# improved_sample-and-hold.net
KiCad netlist of a schematic drawn in EAGLE
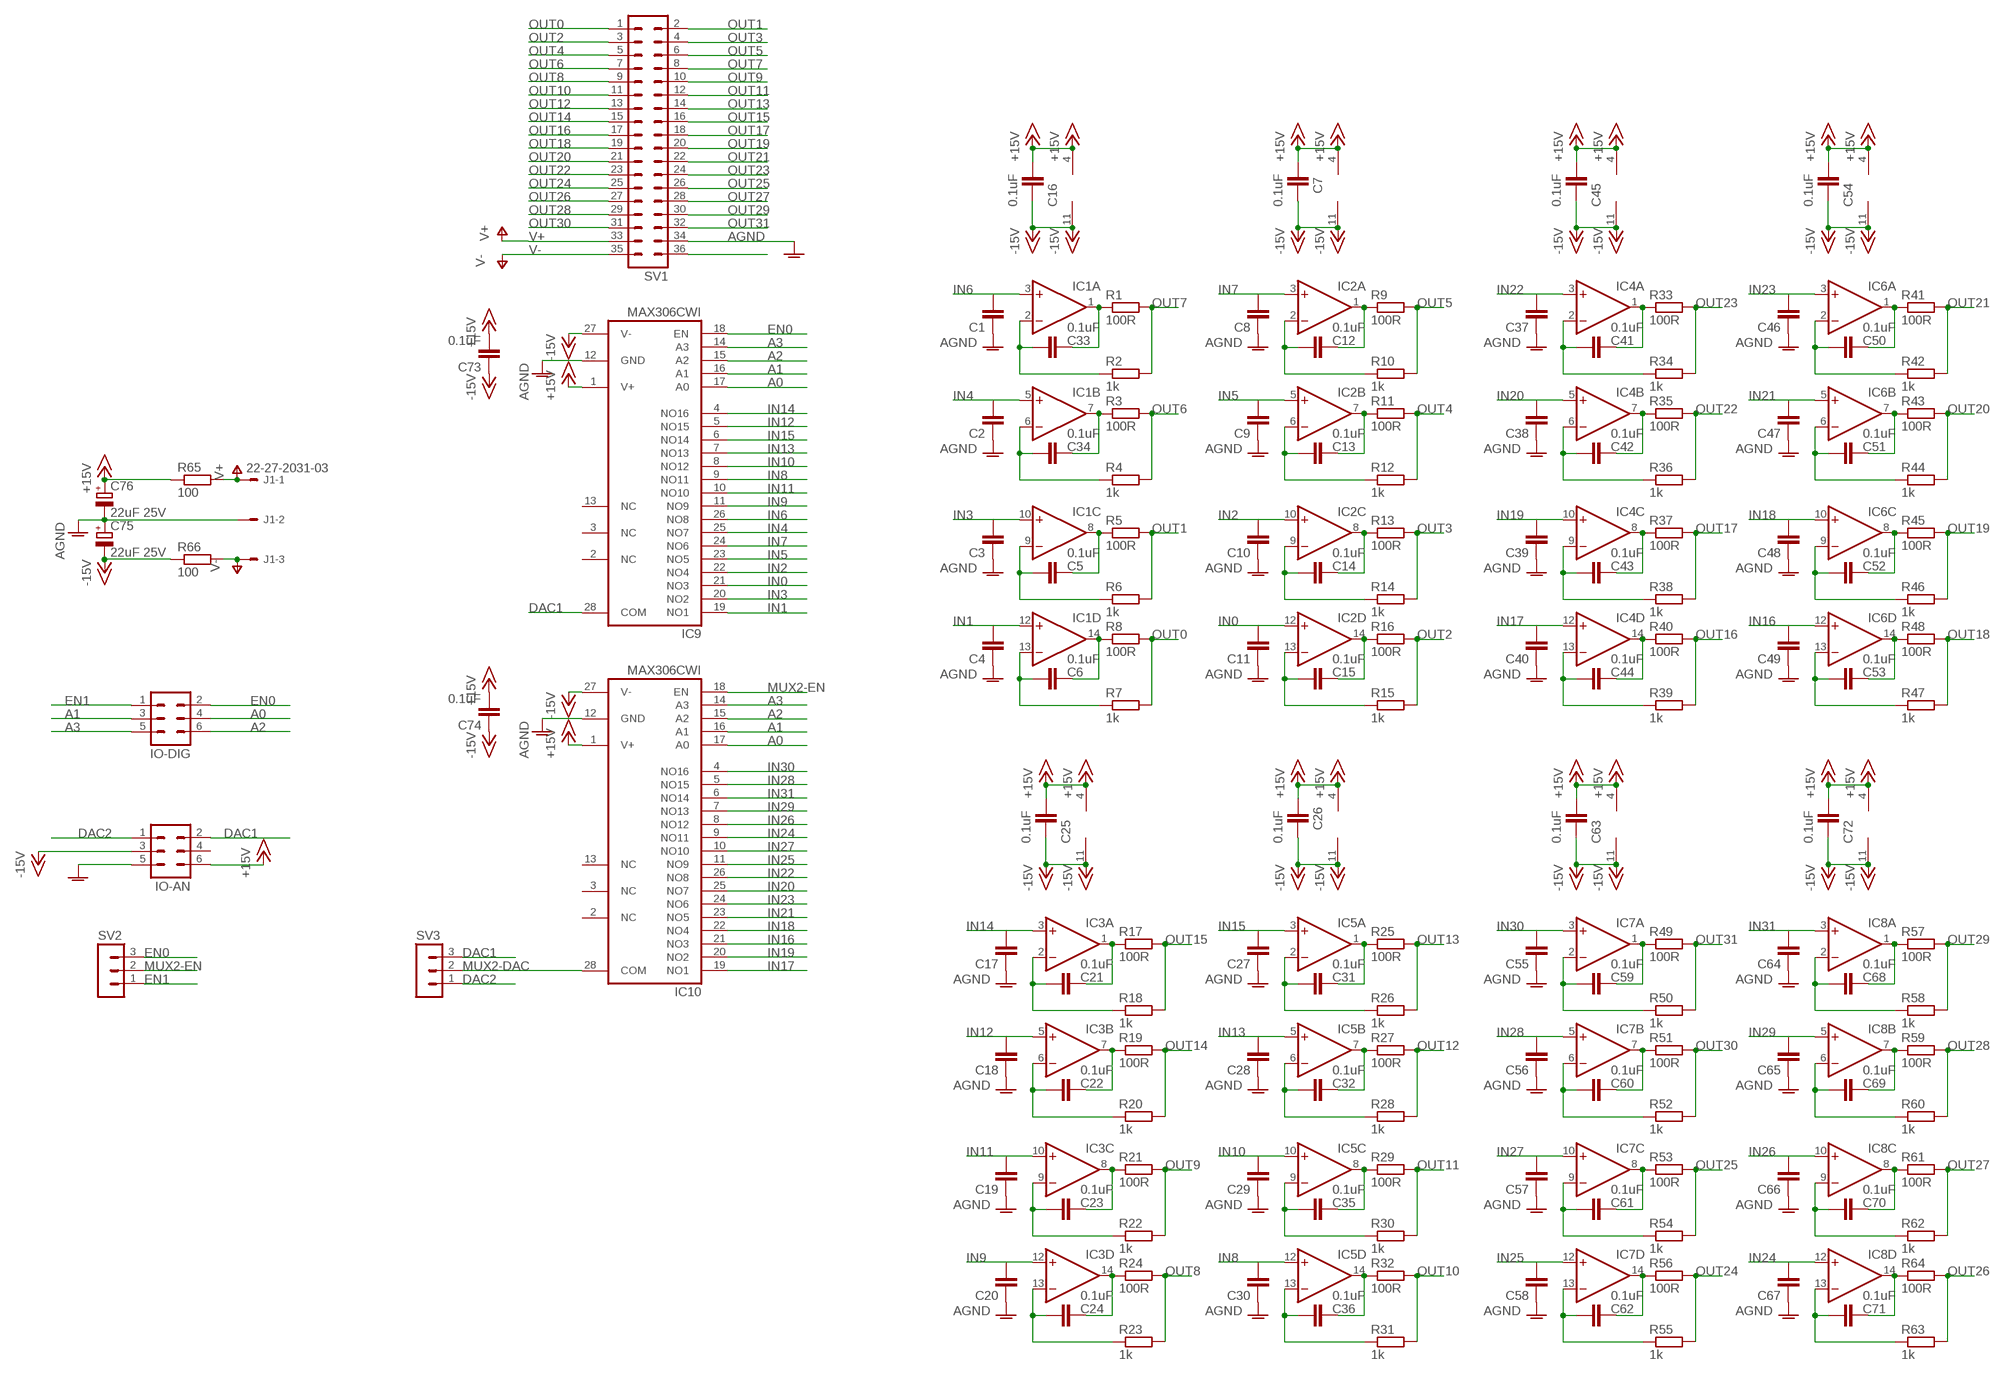
[diagram p0: schematic, sheet 1]

(export (version "E")
  (design (tool "Eeschema 10.0.6"))
  (components
    (comp (ref "C1")
      (value "C-EUC1206")
      (footprint "eagle-import:C1206")
      (libsource (lib "eagle-import") (part "C-EUC1206"))
    )
    (comp (ref "C2")
      (value "C-EUC1206")
      (footprint "eagle-import:C1206")
      (libsource (lib "eagle-import") (part "C-EUC1206"))
    )
    (comp (ref "C3")
      (value "C-EUC1206")
      (footprint "eagle-import:C1206")
      (libsource (lib "eagle-import") (part "C-EUC1206"))
    )
    (comp (ref "C4")
      (value "C-EUC1206")
      (footprint "eagle-import:C1206")
      (libsource (lib "eagle-import") (part "C-EUC1206"))
    )
    (comp (ref "C5")
      (value "0.1uF")
      (footprint "eagle-import:C0603")
      (libsource (lib "eagle-import") (part "C-EUC0603"))
    )
    (comp (ref "C6")
      (value "0.1uF")
      (footprint "eagle-import:C0603")
      (libsource (lib "eagle-import") (part "C-EUC0603"))
    )
    (comp (ref "C7")
      (value "0.1uF")
      (footprint "eagle-import:C0603")
      (libsource (lib "eagle-import") (part "C-EUC0603"))
    )
    (comp (ref "C8")
      (value "C-EUC1206")
      (footprint "eagle-import:C1206")
      (libsource (lib "eagle-import") (part "C-EUC1206"))
    )
    (comp (ref "C9")
      (value "C-EUC1206")
      (footprint "eagle-import:C1206")
      (libsource (lib "eagle-import") (part "C-EUC1206"))
    )
    (comp (ref "C10")
      (value "C-EUC1206")
      (footprint "eagle-import:C1206")
      (libsource (lib "eagle-import") (part "C-EUC1206"))
    )
    (comp (ref "C11")
      (value "C-EUC1206")
      (footprint "eagle-import:C1206")
      (libsource (lib "eagle-import") (part "C-EUC1206"))
    )
    (comp (ref "C12")
      (value "0.1uF")
      (footprint "eagle-import:C0603")
      (libsource (lib "eagle-import") (part "C-EUC0603"))
    )
    (comp (ref "C13")
      (value "0.1uF")
      (footprint "eagle-import:C0603")
      (libsource (lib "eagle-import") (part "C-EUC0603"))
    )
    (comp (ref "C14")
      (value "0.1uF")
      (footprint "eagle-import:C0603")
      (libsource (lib "eagle-import") (part "C-EUC0603"))
    )
    (comp (ref "C15")
      (value "0.1uF")
      (footprint "eagle-import:C0603")
      (libsource (lib "eagle-import") (part "C-EUC0603"))
    )
    (comp (ref "C16")
      (value "0.1uF")
      (footprint "eagle-import:C0603")
      (libsource (lib "eagle-import") (part "C-EUC0603"))
    )
    (comp (ref "C17")
      (value "C-EUC1206")
      (footprint "eagle-import:C1206")
      (libsource (lib "eagle-import") (part "C-EUC1206"))
    )
    (comp (ref "C18")
      (value "C-EUC1206")
      (footprint "eagle-import:C1206")
      (libsource (lib "eagle-import") (part "C-EUC1206"))
    )
    (comp (ref "C19")
      (value "C-EUC1206")
      (footprint "eagle-import:C1206")
      (libsource (lib "eagle-import") (part "C-EUC1206"))
    )
    (comp (ref "C20")
      (value "C-EUC1206")
      (footprint "eagle-import:C1206")
      (libsource (lib "eagle-import") (part "C-EUC1206"))
    )
    (comp (ref "C21")
      (value "0.1uF")
      (footprint "eagle-import:C0603")
      (libsource (lib "eagle-import") (part "C-EUC0603"))
    )
    (comp (ref "C22")
      (value "0.1uF")
      (footprint "eagle-import:C0603")
      (libsource (lib "eagle-import") (part "C-EUC0603"))
    )
    (comp (ref "C23")
      (value "0.1uF")
      (footprint "eagle-import:C0603")
      (libsource (lib "eagle-import") (part "C-EUC0603"))
    )
    (comp (ref "C24")
      (value "0.1uF")
      (footprint "eagle-import:C0603")
      (libsource (lib "eagle-import") (part "C-EUC0603"))
    )
    (comp (ref "C25")
      (value "0.1uF")
      (footprint "eagle-import:C0603")
      (libsource (lib "eagle-import") (part "C-EUC0603"))
    )
    (comp (ref "C26")
      (value "0.1uF")
      (footprint "eagle-import:C0603")
      (libsource (lib "eagle-import") (part "C-EUC0603"))
    )
    (comp (ref "C27")
      (value "C-EUC1206")
      (footprint "eagle-import:C1206")
      (libsource (lib "eagle-import") (part "C-EUC1206"))
    )
    (comp (ref "C28")
      (value "C-EUC1206")
      (footprint "eagle-import:C1206")
      (libsource (lib "eagle-import") (part "C-EUC1206"))
    )
    (comp (ref "C29")
      (value "C-EUC1206")
      (footprint "eagle-import:C1206")
      (libsource (lib "eagle-import") (part "C-EUC1206"))
    )
    (comp (ref "C30")
      (value "C-EUC1206")
      (footprint "eagle-import:C1206")
      (libsource (lib "eagle-import") (part "C-EUC1206"))
    )
    (comp (ref "C31")
      (value "0.1uF")
      (footprint "eagle-import:C0603")
      (libsource (lib "eagle-import") (part "C-EUC0603"))
    )
    (comp (ref "C32")
      (value "0.1uF")
      (footprint "eagle-import:C0603")
      (libsource (lib "eagle-import") (part "C-EUC0603"))
    )
    (comp (ref "C33")
      (value "0.1uF")
      (footprint "eagle-import:C0603")
      (libsource (lib "eagle-import") (part "C-EUC0603"))
    )
    (comp (ref "C34")
      (value "0.1uF")
      (footprint "eagle-import:C0603")
      (libsource (lib "eagle-import") (part "C-EUC0603"))
    )
    (comp (ref "C35")
      (value "0.1uF")
      (footprint "eagle-import:C0603")
      (libsource (lib "eagle-import") (part "C-EUC0603"))
    )
    (comp (ref "C36")
      (value "0.1uF")
      (footprint "eagle-import:C0603")
      (libsource (lib "eagle-import") (part "C-EUC0603"))
    )
    (comp (ref "C37")
      (value "C-EUC1206")
      (footprint "eagle-import:C1206")
      (libsource (lib "eagle-import") (part "C-EUC1206"))
    )
    (comp (ref "C38")
      (value "C-EUC1206")
      (footprint "eagle-import:C1206")
      (libsource (lib "eagle-import") (part "C-EUC1206"))
    )
    (comp (ref "C39")
      (value "C-EUC1206")
      (footprint "eagle-import:C1206")
      (libsource (lib "eagle-import") (part "C-EUC1206"))
    )
    (comp (ref "C40")
      (value "C-EUC1206")
      (footprint "eagle-import:C1206")
      (libsource (lib "eagle-import") (part "C-EUC1206"))
    )
    (comp (ref "C41")
      (value "0.1uF")
      (footprint "eagle-import:C0603")
      (libsource (lib "eagle-import") (part "C-EUC0603"))
    )
    (comp (ref "C42")
      (value "0.1uF")
      (footprint "eagle-import:C0603")
      (libsource (lib "eagle-import") (part "C-EUC0603"))
    )
    (comp (ref "C43")
      (value "0.1uF")
      (footprint "eagle-import:C0603")
      (libsource (lib "eagle-import") (part "C-EUC0603"))
    )
    (comp (ref "C44")
      (value "0.1uF")
      (footprint "eagle-import:C0603")
      (libsource (lib "eagle-import") (part "C-EUC0603"))
    )
    (comp (ref "C45")
      (value "0.1uF")
      (footprint "eagle-import:C0603")
      (libsource (lib "eagle-import") (part "C-EUC0603"))
    )
    (comp (ref "C46")
      (value "C-EUC1206")
      (footprint "eagle-import:C1206")
      (libsource (lib "eagle-import") (part "C-EUC1206"))
    )
    (comp (ref "C47")
      (value "C-EUC1206")
      (footprint "eagle-import:C1206")
      (libsource (lib "eagle-import") (part "C-EUC1206"))
    )
    (comp (ref "C48")
      (value "C-EUC1206")
      (footprint "eagle-import:C1206")
      (libsource (lib "eagle-import") (part "C-EUC1206"))
    )
    (comp (ref "C49")
      (value "C-EUC1206")
      (footprint "eagle-import:C1206")
      (libsource (lib "eagle-import") (part "C-EUC1206"))
    )
    (comp (ref "C50")
      (value "0.1uF")
      (footprint "eagle-import:C0603")
      (libsource (lib "eagle-import") (part "C-EUC0603"))
    )
    (comp (ref "C51")
      (value "0.1uF")
      (footprint "eagle-import:C0603")
      (libsource (lib "eagle-import") (part "C-EUC0603"))
    )
    (comp (ref "C52")
      (value "0.1uF")
      (footprint "eagle-import:C0603")
      (libsource (lib "eagle-import") (part "C-EUC0603"))
    )
    (comp (ref "C53")
      (value "0.1uF")
      (footprint "eagle-import:C0603")
      (libsource (lib "eagle-import") (part "C-EUC0603"))
    )
    (comp (ref "C54")
      (value "0.1uF")
      (footprint "eagle-import:C0603")
      (libsource (lib "eagle-import") (part "C-EUC0603"))
    )
    (comp (ref "C55")
      (value "C-EUC1206")
      (footprint "eagle-import:C1206")
      (libsource (lib "eagle-import") (part "C-EUC1206"))
    )
    (comp (ref "C56")
      (value "C-EUC1206")
      (footprint "eagle-import:C1206")
      (libsource (lib "eagle-import") (part "C-EUC1206"))
    )
    (comp (ref "C57")
      (value "C-EUC1206")
      (footprint "eagle-import:C1206")
      (libsource (lib "eagle-import") (part "C-EUC1206"))
    )
    (comp (ref "C58")
      (value "C-EUC1206")
      (footprint "eagle-import:C1206")
      (libsource (lib "eagle-import") (part "C-EUC1206"))
    )
    (comp (ref "C59")
      (value "0.1uF")
      (footprint "eagle-import:C0603")
      (libsource (lib "eagle-import") (part "C-EUC0603"))
    )
    (comp (ref "C60")
      (value "0.1uF")
      (footprint "eagle-import:C0603")
      (libsource (lib "eagle-import") (part "C-EUC0603"))
    )
    (comp (ref "C61")
      (value "0.1uF")
      (footprint "eagle-import:C0603")
      (libsource (lib "eagle-import") (part "C-EUC0603"))
    )
    (comp (ref "C62")
      (value "0.1uF")
      (footprint "eagle-import:C0603")
      (libsource (lib "eagle-import") (part "C-EUC0603"))
    )
    (comp (ref "C63")
      (value "0.1uF")
      (footprint "eagle-import:C0603")
      (libsource (lib "eagle-import") (part "C-EUC0603"))
    )
    (comp (ref "C64")
      (value "C-EUC1206")
      (footprint "eagle-import:C1206")
      (libsource (lib "eagle-import") (part "C-EUC1206"))
    )
    (comp (ref "C65")
      (value "C-EUC1206")
      (footprint "eagle-import:C1206")
      (libsource (lib "eagle-import") (part "C-EUC1206"))
    )
    (comp (ref "C66")
      (value "C-EUC1206")
      (footprint "eagle-import:C1206")
      (libsource (lib "eagle-import") (part "C-EUC1206"))
    )
    (comp (ref "C67")
      (value "C-EUC1206")
      (footprint "eagle-import:C1206")
      (libsource (lib "eagle-import") (part "C-EUC1206"))
    )
    (comp (ref "C68")
      (value "0.1uF")
      (footprint "eagle-import:C0603")
      (libsource (lib "eagle-import") (part "C-EUC0603"))
    )
    (comp (ref "C69")
      (value "0.1uF")
      (footprint "eagle-import:C0603")
      (libsource (lib "eagle-import") (part "C-EUC0603"))
    )
    (comp (ref "C70")
      (value "0.1uF")
      (footprint "eagle-import:C0603")
      (libsource (lib "eagle-import") (part "C-EUC0603"))
    )
    (comp (ref "C71")
      (value "0.1uF")
      (footprint "eagle-import:C0603")
      (libsource (lib "eagle-import") (part "C-EUC0603"))
    )
    (comp (ref "C72")
      (value "0.1uF")
      (footprint "eagle-import:C0603")
      (libsource (lib "eagle-import") (part "C-EUC0603"))
    )
    (comp (ref "C73")
      (value "0.1uF")
      (footprint "eagle-import:C0603")
      (libsource (lib "eagle-import") (part "C-EUC0603"))
    )
    (comp (ref "C74")
      (value "0.1uF")
      (footprint "eagle-import:C0603")
      (libsource (lib "eagle-import") (part "C-EUC0603"))
    )
    (comp (ref "C75")
      (value "22uF 25V")
      (footprint "eagle-import:E2-5")
      (libsource (lib "eagle-import") (part "CPOL-EUE2-5"))
    )
    (comp (ref "C76")
      (value "22uF 25V")
      (footprint "eagle-import:E2-5")
      (libsource (lib "eagle-import") (part "CPOL-EUE2-5"))
    )
    (comp (ref "IC1")
      (value "TL074D")
      (footprint "eagle-import:SO14")
      (libsource (lib "eagle-import") (part "TL074D"))
    )
    (comp (ref "IC2")
      (value "TL074D")
      (footprint "eagle-import:SO14")
      (libsource (lib "eagle-import") (part "TL074D"))
    )
    (comp (ref "IC3")
      (value "TL074D")
      (footprint "eagle-import:SO14")
      (libsource (lib "eagle-import") (part "TL074D"))
    )
    (comp (ref "IC4")
      (value "TL074D")
      (footprint "eagle-import:SO14")
      (libsource (lib "eagle-import") (part "TL074D"))
    )
    (comp (ref "IC5")
      (value "TL074D")
      (footprint "eagle-import:SO14")
      (libsource (lib "eagle-import") (part "TL074D"))
    )
    (comp (ref "IC6")
      (value "TL074D")
      (footprint "eagle-import:SO14")
      (libsource (lib "eagle-import") (part "TL074D"))
    )
    (comp (ref "IC7")
      (value "TL074D")
      (footprint "eagle-import:SO14")
      (libsource (lib "eagle-import") (part "TL074D"))
    )
    (comp (ref "IC8")
      (value "TL074D")
      (footprint "eagle-import:SO14")
      (libsource (lib "eagle-import") (part "TL074D"))
    )
    (comp (ref "IC9")
      (value "MAX306CWI")
      (footprint "eagle-import:SO28L")
      (fields (field (name "MF") "MAXIM"))
      (libsource (lib "eagle-import") (part "MAX306CWI"))
    )
    (comp (ref "IC10")
      (value "MAX306CWI")
      (footprint "eagle-import:SO28L")
      (fields (field (name "MF") "MAXIM"))
      (libsource (lib "eagle-import") (part "MAX306CWI"))
    )
    (comp (ref "IO-AN")
      (value "MA03-2")
      (footprint "eagle-import:MA03-2")
      (libsource (lib "eagle-import") (part "MA03-2"))
    )
    (comp (ref "IO-DIG")
      (value "MA03-2")
      (footprint "eagle-import:MA03-2")
      (libsource (lib "eagle-import") (part "MA03-2"))
    )
    (comp (ref "J1")
      (value "22-27-2031-03")
      (footprint "eagle-import:6410-03")
      (libsource (lib "eagle-import") (part "22-?-0327-2031"))
    )
    (comp (ref "R1")
      (value "100R")
      (footprint "eagle-import:R0603")
      (libsource (lib "eagle-import") (part "R-EU_R0603"))
    )
    (comp (ref "R2")
      (value "1k")
      (footprint "eagle-import:R0603")
      (libsource (lib "eagle-import") (part "R-EU_R0603"))
    )
    (comp (ref "R3")
      (value "100R")
      (footprint "eagle-import:R0603")
      (libsource (lib "eagle-import") (part "R-EU_R0603"))
    )
    (comp (ref "R4")
      (value "1k")
      (footprint "eagle-import:R0603")
      (libsource (lib "eagle-import") (part "R-EU_R0603"))
    )
    (comp (ref "R5")
      (value "100R")
      (footprint "eagle-import:R0603")
      (libsource (lib "eagle-import") (part "R-EU_R0603"))
    )
    (comp (ref "R6")
      (value "1k")
      (footprint "eagle-import:R0603")
      (libsource (lib "eagle-import") (part "R-EU_R0603"))
    )
    (comp (ref "R7")
      (value "1k")
      (footprint "eagle-import:R0603")
      (libsource (lib "eagle-import") (part "R-EU_R0603"))
    )
    (comp (ref "R8")
      (value "100R")
      (footprint "eagle-import:R0603")
      (libsource (lib "eagle-import") (part "R-EU_R0603"))
    )
    (comp (ref "R9")
      (value "100R")
      (footprint "eagle-import:R0603")
      (libsource (lib "eagle-import") (part "R-EU_R0603"))
    )
    (comp (ref "R10")
      (value "1k")
      (footprint "eagle-import:R0603")
      (libsource (lib "eagle-import") (part "R-EU_R0603"))
    )
    (comp (ref "R11")
      (value "100R")
      (footprint "eagle-import:R0603")
      (libsource (lib "eagle-import") (part "R-EU_R0603"))
    )
    (comp (ref "R12")
      (value "1k")
      (footprint "eagle-import:R0603")
      (libsource (lib "eagle-import") (part "R-EU_R0603"))
    )
    (comp (ref "R13")
      (value "100R")
      (footprint "eagle-import:R0603")
      (libsource (lib "eagle-import") (part "R-EU_R0603"))
    )
    (comp (ref "R14")
      (value "1k")
      (footprint "eagle-import:R0603")
      (libsource (lib "eagle-import") (part "R-EU_R0603"))
    )
    (comp (ref "R15")
      (value "1k")
      (footprint "eagle-import:R0603")
      (libsource (lib "eagle-import") (part "R-EU_R0603"))
    )
    (comp (ref "R16")
      (value "100R")
      (footprint "eagle-import:R0603")
      (libsource (lib "eagle-import") (part "R-EU_R0603"))
    )
    (comp (ref "R17")
      (value "100R")
      (footprint "eagle-import:R0603")
      (libsource (lib "eagle-import") (part "R-EU_R0603"))
    )
    (comp (ref "R18")
      (value "1k")
      (footprint "eagle-import:R0603")
      (libsource (lib "eagle-import") (part "R-EU_R0603"))
    )
    (comp (ref "R19")
      (value "100R")
      (footprint "eagle-import:R0603")
      (libsource (lib "eagle-import") (part "R-EU_R0603"))
    )
    (comp (ref "R20")
      (value "1k")
      (footprint "eagle-import:R0603")
      (libsource (lib "eagle-import") (part "R-EU_R0603"))
    )
    (comp (ref "R21")
      (value "100R")
      (footprint "eagle-import:R0603")
      (libsource (lib "eagle-import") (part "R-EU_R0603"))
    )
    (comp (ref "R22")
      (value "1k")
      (footprint "eagle-import:R0603")
      (libsource (lib "eagle-import") (part "R-EU_R0603"))
    )
    (comp (ref "R23")
      (value "1k")
      (footprint "eagle-import:R0603")
      (libsource (lib "eagle-import") (part "R-EU_R0603"))
    )
    (comp (ref "R24")
      (value "100R")
      (footprint "eagle-import:R0603")
      (libsource (lib "eagle-import") (part "R-EU_R0603"))
    )
    (comp (ref "R25")
      (value "100R")
      (footprint "eagle-import:R0603")
      (libsource (lib "eagle-import") (part "R-EU_R0603"))
    )
    (comp (ref "R26")
      (value "1k")
      (footprint "eagle-import:R0603")
      (libsource (lib "eagle-import") (part "R-EU_R0603"))
    )
    (comp (ref "R27")
      (value "100R")
      (footprint "eagle-import:R0603")
      (libsource (lib "eagle-import") (part "R-EU_R0603"))
    )
    (comp (ref "R28")
      (value "1k")
      (footprint "eagle-import:R0603")
      (libsource (lib "eagle-import") (part "R-EU_R0603"))
    )
    (comp (ref "R29")
      (value "100R")
      (footprint "eagle-import:R0603")
      (libsource (lib "eagle-import") (part "R-EU_R0603"))
    )
    (comp (ref "R30")
      (value "1k")
      (footprint "eagle-import:R0603")
      (libsource (lib "eagle-import") (part "R-EU_R0603"))
    )
    (comp (ref "R31")
      (value "1k")
      (footprint "eagle-import:R0603")
      (libsource (lib "eagle-import") (part "R-EU_R0603"))
    )
    (comp (ref "R32")
      (value "100R")
      (footprint "eagle-import:R0603")
      (libsource (lib "eagle-import") (part "R-EU_R0603"))
    )
    (comp (ref "R33")
      (value "100R")
      (footprint "eagle-import:R0603")
      (libsource (lib "eagle-import") (part "R-EU_R0603"))
    )
    (comp (ref "R34")
      (value "1k")
      (footprint "eagle-import:R0603")
      (libsource (lib "eagle-import") (part "R-EU_R0603"))
    )
    (comp (ref "R35")
      (value "100R")
      (footprint "eagle-import:R0603")
      (libsource (lib "eagle-import") (part "R-EU_R0603"))
    )
    (comp (ref "R36")
      (value "1k")
      (footprint "eagle-import:R0603")
      (libsource (lib "eagle-import") (part "R-EU_R0603"))
    )
    (comp (ref "R37")
      (value "100R")
      (footprint "eagle-import:R0603")
      (libsource (lib "eagle-import") (part "R-EU_R0603"))
    )
    (comp (ref "R38")
      (value "1k")
      (footprint "eagle-import:R0603")
      (libsource (lib "eagle-import") (part "R-EU_R0603"))
    )
    (comp (ref "R39")
      (value "1k")
      (footprint "eagle-import:R0603")
      (libsource (lib "eagle-import") (part "R-EU_R0603"))
    )
    (comp (ref "R40")
      (value "100R")
      (footprint "eagle-import:R0603")
      (libsource (lib "eagle-import") (part "R-EU_R0603"))
    )
    (comp (ref "R41")
      (value "100R")
      (footprint "eagle-import:R0603")
      (libsource (lib "eagle-import") (part "R-EU_R0603"))
    )
    (comp (ref "R42")
      (value "1k")
      (footprint "eagle-import:R0603")
      (libsource (lib "eagle-import") (part "R-EU_R0603"))
    )
    (comp (ref "R43")
      (value "100R")
      (footprint "eagle-import:R0603")
      (libsource (lib "eagle-import") (part "R-EU_R0603"))
    )
    (comp (ref "R44")
      (value "1k")
      (footprint "eagle-import:R0603")
      (libsource (lib "eagle-import") (part "R-EU_R0603"))
    )
    (comp (ref "R45")
      (value "100R")
      (footprint "eagle-import:R0603")
      (libsource (lib "eagle-import") (part "R-EU_R0603"))
    )
    (comp (ref "R46")
      (value "1k")
      (footprint "eagle-import:R0603")
      (libsource (lib "eagle-import") (part "R-EU_R0603"))
    )
    (comp (ref "R47")
      (value "1k")
      (footprint "eagle-import:R0603")
      (libsource (lib "eagle-import") (part "R-EU_R0603"))
    )
    (comp (ref "R48")
      (value "100R")
      (footprint "eagle-import:R0603")
      (libsource (lib "eagle-import") (part "R-EU_R0603"))
    )
    (comp (ref "R49")
      (value "100R")
      (footprint "eagle-import:R0603")
      (libsource (lib "eagle-import") (part "R-EU_R0603"))
    )
    (comp (ref "R50")
      (value "1k")
      (footprint "eagle-import:R0603")
      (libsource (lib "eagle-import") (part "R-EU_R0603"))
    )
    (comp (ref "R51")
      (value "100R")
      (footprint "eagle-import:R0603")
      (libsource (lib "eagle-import") (part "R-EU_R0603"))
    )
    (comp (ref "R52")
      (value "1k")
      (footprint "eagle-import:R0603")
      (libsource (lib "eagle-import") (part "R-EU_R0603"))
    )
    (comp (ref "R53")
      (value "100R")
      (footprint "eagle-import:R0603")
      (libsource (lib "eagle-import") (part "R-EU_R0603"))
    )
    (comp (ref "R54")
      (value "1k")
      (footprint "eagle-import:R0603")
      (libsource (lib "eagle-import") (part "R-EU_R0603"))
    )
    (comp (ref "R55")
      (value "1k")
      (footprint "eagle-import:R0603")
      (libsource (lib "eagle-import") (part "R-EU_R0603"))
    )
    (comp (ref "R56")
      (value "100R")
      (footprint "eagle-import:R0603")
      (libsource (lib "eagle-import") (part "R-EU_R0603"))
    )
    (comp (ref "R57")
      (value "100R")
      (footprint "eagle-import:R0603")
      (libsource (lib "eagle-import") (part "R-EU_R0603"))
    )
    (comp (ref "R58")
      (value "1k")
      (footprint "eagle-import:R0603")
      (libsource (lib "eagle-import") (part "R-EU_R0603"))
    )
    (comp (ref "R59")
      (value "100R")
      (footprint "eagle-import:R0603")
      (libsource (lib "eagle-import") (part "R-EU_R0603"))
    )
    (comp (ref "R60")
      (value "1k")
      (footprint "eagle-import:R0603")
      (libsource (lib "eagle-import") (part "R-EU_R0603"))
    )
    (comp (ref "R61")
      (value "100R")
      (footprint "eagle-import:R0603")
      (libsource (lib "eagle-import") (part "R-EU_R0603"))
    )
    (comp (ref "R62")
      (value "1k")
      (footprint "eagle-import:R0603")
      (libsource (lib "eagle-import") (part "R-EU_R0603"))
    )
    (comp (ref "R63")
      (value "1k")
      (footprint "eagle-import:R0603")
      (libsource (lib "eagle-import") (part "R-EU_R0603"))
    )
    (comp (ref "R64")
      (value "100R")
      (footprint "eagle-import:R0603")
      (libsource (lib "eagle-import") (part "R-EU_R0603"))
    )
    (comp (ref "R65")
      (value "100")
      (footprint "eagle-import:0207_7")
      (libsource (lib "eagle-import") (part "R-EU_0207/7"))
    )
    (comp (ref "R66")
      (value "100")
      (footprint "eagle-import:0207_7")
      (libsource (lib "eagle-import") (part "R-EU_0207/7"))
    )
    (comp (ref "SV1")
      (value "MA18-2")
      (footprint "eagle-import:MA18-2")
      (libsource (lib "eagle-import") (part "MA18-2"))
    )
    (comp (ref "SV2")
      (value "MA03-1")
      (footprint "eagle-import:MA03-1")
      (libsource (lib "eagle-import") (part "MA03-1"))
    )
    (comp (ref "SV3")
      (value "MA03-1")
      (footprint "eagle-import:MA03-1")
      (libsource (lib "eagle-import") (part "MA03-1"))
    )
  )
  (nets
    (net (code "1") (name "+15V") (class "Default")
      (node (ref "C16") (pin "1") (pinfunction "1_1") (pintype "passive"))
      (node (ref "C25") (pin "1") (pinfunction "1_1") (pintype "passive"))
      (node (ref "C26") (pin "1") (pinfunction "1_1") (pintype "passive"))
      (node (ref "C45") (pin "1") (pinfunction "1_1") (pintype "passive"))
      (node (ref "C54") (pin "1") (pinfunction "1_1") (pintype "passive"))
      (node (ref "C63") (pin "1") (pinfunction "1_1") (pintype "passive"))
      (node (ref "C7") (pin "1") (pinfunction "1_1") (pintype "passive"))
      (node (ref "C72") (pin "1") (pinfunction "1_1") (pintype "passive"))
      (node (ref "C73") (pin "2") (pinfunction "2_2") (pintype "passive"))
      (node (ref "C74") (pin "2") (pinfunction "2_2") (pintype "passive"))
      (node (ref "C76") (pin "+") (pinfunction "+_+") (pintype "passive"))
      (node (ref "IC1") (pin "4") (pinfunction "V+_4") (pintype "power_in"))
      (node (ref "IC10") (pin "1") (pinfunction "V+_1") (pintype "power_in"))
      (node (ref "IC2") (pin "4") (pinfunction "V+_4") (pintype "power_in"))
      (node (ref "IC3") (pin "4") (pinfunction "V+_4") (pintype "power_in"))
      (node (ref "IC4") (pin "4") (pinfunction "V+_4") (pintype "power_in"))
      (node (ref "IC5") (pin "4") (pinfunction "V+_4") (pintype "power_in"))
      (node (ref "IC6") (pin "4") (pinfunction "V+_4") (pintype "power_in"))
      (node (ref "IC7") (pin "4") (pinfunction "V+_4") (pintype "power_in"))
      (node (ref "IC8") (pin "4") (pinfunction "V+_4") (pintype "power_in"))
      (node (ref "IC9") (pin "1") (pinfunction "V+_1") (pintype "power_in"))
      (node (ref "IO-AN") (pin "6") (pinfunction "6_6") (pintype "passive"))
      (node (ref "R65") (pin "1") (pinfunction "1_1") (pintype "passive"))
    )
    (net (code "2") (name "-15V") (class "Default")
      (node (ref "C16") (pin "2") (pinfunction "2_2") (pintype "passive"))
      (node (ref "C25") (pin "2") (pinfunction "2_2") (pintype "passive"))
      (node (ref "C26") (pin "2") (pinfunction "2_2") (pintype "passive"))
      (node (ref "C45") (pin "2") (pinfunction "2_2") (pintype "passive"))
      (node (ref "C54") (pin "2") (pinfunction "2_2") (pintype "passive"))
      (node (ref "C63") (pin "2") (pinfunction "2_2") (pintype "passive"))
      (node (ref "C7") (pin "2") (pinfunction "2_2") (pintype "passive"))
      (node (ref "C72") (pin "2") (pinfunction "2_2") (pintype "passive"))
      (node (ref "C73") (pin "1") (pinfunction "1_1") (pintype "passive"))
      (node (ref "C74") (pin "1") (pinfunction "1_1") (pintype "passive"))
      (node (ref "C75") (pin "-") (pinfunction "-_-") (pintype "passive"))
      (node (ref "IC1") (pin "11") (pinfunction "V-_11") (pintype "power_in"))
      (node (ref "IC10") (pin "27") (pinfunction "V-_27") (pintype "power_in"))
      (node (ref "IC2") (pin "11") (pinfunction "V-_11") (pintype "power_in"))
      (node (ref "IC3") (pin "11") (pinfunction "V-_11") (pintype "power_in"))
      (node (ref "IC4") (pin "11") (pinfunction "V-_11") (pintype "power_in"))
      (node (ref "IC5") (pin "11") (pinfunction "V-_11") (pintype "power_in"))
      (node (ref "IC6") (pin "11") (pinfunction "V-_11") (pintype "power_in"))
      (node (ref "IC7") (pin "11") (pinfunction "V-_11") (pintype "power_in"))
      (node (ref "IC8") (pin "11") (pinfunction "V-_11") (pintype "power_in"))
      (node (ref "IC9") (pin "27") (pinfunction "V-_27") (pintype "power_in"))
      (node (ref "IO-AN") (pin "3") (pinfunction "3_3") (pintype "passive"))
      (node (ref "R66") (pin "1") (pinfunction "1_1") (pintype "passive"))
    )
    (net (code "3") (name "/A0") (class "Default")
      (node (ref "IC10") (pin "17") (pinfunction "A0_17") (pintype "input"))
      (node (ref "IC9") (pin "17") (pinfunction "A0_17") (pintype "input"))
      (node (ref "IO-DIG") (pin "4") (pinfunction "4_4") (pintype "passive"))
    )
    (net (code "4") (name "/A1") (class "Default")
      (node (ref "IC10") (pin "16") (pinfunction "A1_16") (pintype "input"))
      (node (ref "IC9") (pin "16") (pinfunction "A1_16") (pintype "input"))
      (node (ref "IO-DIG") (pin "3") (pinfunction "3_3") (pintype "passive"))
    )
    (net (code "5") (name "/A2") (class "Default")
      (node (ref "IC10") (pin "15") (pinfunction "A2_15") (pintype "input"))
      (node (ref "IC9") (pin "15") (pinfunction "A2_15") (pintype "input"))
      (node (ref "IO-DIG") (pin "6") (pinfunction "6_6") (pintype "passive"))
    )
    (net (code "6") (name "/A3") (class "Default")
      (node (ref "IC10") (pin "14") (pinfunction "A3_14") (pintype "input"))
      (node (ref "IC9") (pin "14") (pinfunction "A3_14") (pintype "input"))
      (node (ref "IO-DIG") (pin "5") (pinfunction "5_5") (pintype "passive"))
    )
    (net (code "7") (name "/DAC1") (class "Default")
      (node (ref "IC9") (pin "28") (pinfunction "COM_28") (pintype "passive"))
      (node (ref "IO-AN") (pin "2") (pinfunction "2_2") (pintype "passive"))
      (node (ref "SV3") (pin "3") (pinfunction "3_3") (pintype "passive"))
    )
    (net (code "8") (name "/DAC2") (class "Default")
      (node (ref "IO-AN") (pin "1") (pinfunction "1_1") (pintype "passive"))
      (node (ref "SV3") (pin "1") (pinfunction "1_1") (pintype "passive"))
    )
    (net (code "9") (name "/EN0") (class "Default")
      (node (ref "IC9") (pin "18") (pinfunction "EN_18") (pintype "input"))
      (node (ref "IO-DIG") (pin "2") (pinfunction "2_2") (pintype "passive"))
      (node (ref "SV2") (pin "3") (pinfunction "3_3") (pintype "passive"))
    )
    (net (code "10") (name "/EN1") (class "Default")
      (node (ref "IO-DIG") (pin "1") (pinfunction "1_1") (pintype "passive"))
      (node (ref "SV2") (pin "1") (pinfunction "1_1") (pintype "passive"))
    )
    (net (code "11") (name "/IN0") (class "Default")
      (node (ref "C11") (pin "2") (pinfunction "2_2") (pintype "passive"))
      (node (ref "IC2") (pin "12") (pinfunction "+IN_12") (pintype "input"))
      (node (ref "IC9") (pin "21") (pinfunction "NO3_21") (pintype "passive"))
    )
    (net (code "12") (name "/IN1") (class "Default")
      (node (ref "C4") (pin "2") (pinfunction "2_2") (pintype "passive"))
      (node (ref "IC1") (pin "12") (pinfunction "+IN_12") (pintype "input"))
      (node (ref "IC9") (pin "19") (pinfunction "NO1_19") (pintype "passive"))
    )
    (net (code "13") (name "/IN2") (class "Default")
      (node (ref "C10") (pin "2") (pinfunction "2_2") (pintype "passive"))
      (node (ref "IC2") (pin "10") (pinfunction "+IN_10") (pintype "input"))
      (node (ref "IC9") (pin "22") (pinfunction "NO4_22") (pintype "passive"))
    )
    (net (code "14") (name "/IN3") (class "Default")
      (node (ref "C3") (pin "2") (pinfunction "2_2") (pintype "passive"))
      (node (ref "IC1") (pin "10") (pinfunction "+IN_10") (pintype "input"))
      (node (ref "IC9") (pin "20") (pinfunction "NO2_20") (pintype "passive"))
    )
    (net (code "15") (name "/IN4") (class "Default")
      (node (ref "C2") (pin "2") (pinfunction "2_2") (pintype "passive"))
      (node (ref "IC1") (pin "5") (pinfunction "+IN_5") (pintype "input"))
      (node (ref "IC9") (pin "25") (pinfunction "NO7_25") (pintype "passive"))
    )
    (net (code "16") (name "/IN5") (class "Default")
      (node (ref "C9") (pin "2") (pinfunction "2_2") (pintype "passive"))
      (node (ref "IC2") (pin "5") (pinfunction "+IN_5") (pintype "input"))
      (node (ref "IC9") (pin "23") (pinfunction "NO5_23") (pintype "passive"))
    )
    (net (code "17") (name "/IN6") (class "Default")
      (node (ref "C1") (pin "2") (pinfunction "2_2") (pintype "passive"))
      (node (ref "IC1") (pin "3") (pinfunction "+IN_3") (pintype "input"))
      (node (ref "IC9") (pin "26") (pinfunction "NO8_26") (pintype "passive"))
    )
    (net (code "18") (name "/IN7") (class "Default")
      (node (ref "C8") (pin "2") (pinfunction "2_2") (pintype "passive"))
      (node (ref "IC2") (pin "3") (pinfunction "+IN_3") (pintype "input"))
      (node (ref "IC9") (pin "24") (pinfunction "NO6_24") (pintype "passive"))
    )
    (net (code "19") (name "/IN8") (class "Default")
      (node (ref "C30") (pin "2") (pinfunction "2_2") (pintype "passive"))
      (node (ref "IC5") (pin "12") (pinfunction "+IN_12") (pintype "input"))
      (node (ref "IC9") (pin "9") (pinfunction "NO11_9") (pintype "passive"))
    )
    (net (code "20") (name "/IN9") (class "Default")
      (node (ref "C20") (pin "2") (pinfunction "2_2") (pintype "passive"))
      (node (ref "IC3") (pin "12") (pinfunction "+IN_12") (pintype "input"))
      (node (ref "IC9") (pin "11") (pinfunction "NO9_11") (pintype "passive"))
    )
    (net (code "21") (name "/IN10") (class "Default")
      (node (ref "C29") (pin "2") (pinfunction "2_2") (pintype "passive"))
      (node (ref "IC5") (pin "10") (pinfunction "+IN_10") (pintype "input"))
      (node (ref "IC9") (pin "8") (pinfunction "NO12_8") (pintype "passive"))
    )
    (net (code "22") (name "/IN11") (class "Default")
      (node (ref "C19") (pin "2") (pinfunction "2_2") (pintype "passive"))
      (node (ref "IC3") (pin "10") (pinfunction "+IN_10") (pintype "input"))
      (node (ref "IC9") (pin "10") (pinfunction "NO10_10") (pintype "passive"))
    )
    (net (code "23") (name "/IN12") (class "Default")
      (node (ref "C18") (pin "2") (pinfunction "2_2") (pintype "passive"))
      (node (ref "IC3") (pin "5") (pinfunction "+IN_5") (pintype "input"))
      (node (ref "IC9") (pin "5") (pinfunction "NO15_5") (pintype "passive"))
    )
    (net (code "24") (name "/IN13") (class "Default")
      (node (ref "C28") (pin "2") (pinfunction "2_2") (pintype "passive"))
      (node (ref "IC5") (pin "5") (pinfunction "+IN_5") (pintype "input"))
      (node (ref "IC9") (pin "7") (pinfunction "NO13_7") (pintype "passive"))
    )
    (net (code "25") (name "/IN14") (class "Default")
      (node (ref "C17") (pin "2") (pinfunction "2_2") (pintype "passive"))
      (node (ref "IC3") (pin "3") (pinfunction "+IN_3") (pintype "input"))
      (node (ref "IC9") (pin "4") (pinfunction "NO16_4") (pintype "passive"))
    )
    (net (code "26") (name "/IN15") (class "Default")
      (node (ref "C27") (pin "2") (pinfunction "2_2") (pintype "passive"))
      (node (ref "IC5") (pin "3") (pinfunction "+IN_3") (pintype "input"))
      (node (ref "IC9") (pin "6") (pinfunction "NO14_6") (pintype "passive"))
    )
    (net (code "27") (name "/IN16") (class "Default")
      (node (ref "C49") (pin "2") (pinfunction "2_2") (pintype "passive"))
      (node (ref "IC10") (pin "21") (pinfunction "NO3_21") (pintype "passive"))
      (node (ref "IC6") (pin "12") (pinfunction "+IN_12") (pintype "input"))
    )
    (net (code "28") (name "/IN17") (class "Default")
      (node (ref "C40") (pin "2") (pinfunction "2_2") (pintype "passive"))
      (node (ref "IC10") (pin "19") (pinfunction "NO1_19") (pintype "passive"))
      (node (ref "IC4") (pin "12") (pinfunction "+IN_12") (pintype "input"))
    )
    (net (code "29") (name "/IN18") (class "Default")
      (node (ref "C48") (pin "2") (pinfunction "2_2") (pintype "passive"))
      (node (ref "IC10") (pin "22") (pinfunction "NO4_22") (pintype "passive"))
      (node (ref "IC6") (pin "10") (pinfunction "+IN_10") (pintype "input"))
    )
    (net (code "30") (name "/IN19") (class "Default")
      (node (ref "C39") (pin "2") (pinfunction "2_2") (pintype "passive"))
      (node (ref "IC10") (pin "20") (pinfunction "NO2_20") (pintype "passive"))
      (node (ref "IC4") (pin "10") (pinfunction "+IN_10") (pintype "input"))
    )
    (net (code "31") (name "/IN20") (class "Default")
      (node (ref "C38") (pin "2") (pinfunction "2_2") (pintype "passive"))
      (node (ref "IC10") (pin "25") (pinfunction "NO7_25") (pintype "passive"))
      (node (ref "IC4") (pin "5") (pinfunction "+IN_5") (pintype "input"))
    )
    (net (code "32") (name "/IN21") (class "Default")
      (node (ref "C47") (pin "2") (pinfunction "2_2") (pintype "passive"))
      (node (ref "IC10") (pin "23") (pinfunction "NO5_23") (pintype "passive"))
      (node (ref "IC6") (pin "5") (pinfunction "+IN_5") (pintype "input"))
    )
    (net (code "33") (name "/IN22") (class "Default")
      (node (ref "C37") (pin "2") (pinfunction "2_2") (pintype "passive"))
      (node (ref "IC10") (pin "26") (pinfunction "NO8_26") (pintype "passive"))
      (node (ref "IC4") (pin "3") (pinfunction "+IN_3") (pintype "input"))
    )
    (net (code "34") (name "/IN23") (class "Default")
      (node (ref "C46") (pin "2") (pinfunction "2_2") (pintype "passive"))
      (node (ref "IC10") (pin "24") (pinfunction "NO6_24") (pintype "passive"))
      (node (ref "IC6") (pin "3") (pinfunction "+IN_3") (pintype "input"))
    )
    (net (code "35") (name "/IN24") (class "Default")
      (node (ref "C67") (pin "2") (pinfunction "2_2") (pintype "passive"))
      (node (ref "IC10") (pin "9") (pinfunction "NO11_9") (pintype "passive"))
      (node (ref "IC8") (pin "12") (pinfunction "+IN_12") (pintype "input"))
    )
    (net (code "36") (name "/IN25") (class "Default")
      (node (ref "C58") (pin "2") (pinfunction "2_2") (pintype "passive"))
      (node (ref "IC10") (pin "11") (pinfunction "NO9_11") (pintype "passive"))
      (node (ref "IC7") (pin "12") (pinfunction "+IN_12") (pintype "input"))
    )
    (net (code "37") (name "/IN26") (class "Default")
      (node (ref "C66") (pin "2") (pinfunction "2_2") (pintype "passive"))
      (node (ref "IC10") (pin "8") (pinfunction "NO12_8") (pintype "passive"))
      (node (ref "IC8") (pin "10") (pinfunction "+IN_10") (pintype "input"))
    )
    (net (code "38") (name "/IN27") (class "Default")
      (node (ref "C57") (pin "2") (pinfunction "2_2") (pintype "passive"))
      (node (ref "IC10") (pin "10") (pinfunction "NO10_10") (pintype "passive"))
      (node (ref "IC7") (pin "10") (pinfunction "+IN_10") (pintype "input"))
    )
    (net (code "39") (name "/IN28") (class "Default")
      (node (ref "C56") (pin "2") (pinfunction "2_2") (pintype "passive"))
      (node (ref "IC10") (pin "5") (pinfunction "NO15_5") (pintype "passive"))
      (node (ref "IC7") (pin "5") (pinfunction "+IN_5") (pintype "input"))
    )
    (net (code "40") (name "/IN29") (class "Default")
      (node (ref "C65") (pin "2") (pinfunction "2_2") (pintype "passive"))
      (node (ref "IC10") (pin "7") (pinfunction "NO13_7") (pintype "passive"))
      (node (ref "IC8") (pin "5") (pinfunction "+IN_5") (pintype "input"))
    )
    (net (code "41") (name "/IN30") (class "Default")
      (node (ref "C55") (pin "2") (pinfunction "2_2") (pintype "passive"))
      (node (ref "IC10") (pin "4") (pinfunction "NO16_4") (pintype "passive"))
      (node (ref "IC7") (pin "3") (pinfunction "+IN_3") (pintype "input"))
    )
    (net (code "42") (name "/IN31") (class "Default")
      (node (ref "C64") (pin "2") (pinfunction "2_2") (pintype "passive"))
      (node (ref "IC10") (pin "6") (pinfunction "NO14_6") (pintype "passive"))
      (node (ref "IC8") (pin "3") (pinfunction "+IN_3") (pintype "input"))
    )
    (net (code "43") (name "/MUX2-DAC") (class "Default")
      (node (ref "IC10") (pin "28") (pinfunction "COM_28") (pintype "passive"))
      (node (ref "SV3") (pin "2") (pinfunction "2_2") (pintype "passive"))
    )
    (net (code "44") (name "/MUX2-EN") (class "Default")
      (node (ref "IC10") (pin "18") (pinfunction "EN_18") (pintype "input"))
      (node (ref "SV2") (pin "2") (pinfunction "2_2") (pintype "passive"))
    )
    (net (code "45") (name "/OUT0") (class "Default")
      (node (ref "R7") (pin "2") (pinfunction "2_2") (pintype "passive"))
      (node (ref "R8") (pin "2") (pinfunction "2_2") (pintype "passive"))
      (node (ref "SV1") (pin "1") (pinfunction "1_1") (pintype "passive"))
    )
    (net (code "46") (name "/OUT1") (class "Default")
      (node (ref "R5") (pin "2") (pinfunction "2_2") (pintype "passive"))
      (node (ref "R6") (pin "2") (pinfunction "2_2") (pintype "passive"))
      (node (ref "SV1") (pin "2") (pinfunction "2_2") (pintype "passive"))
    )
    (net (code "47") (name "/OUT2") (class "Default")
      (node (ref "R15") (pin "2") (pinfunction "2_2") (pintype "passive"))
      (node (ref "R16") (pin "2") (pinfunction "2_2") (pintype "passive"))
      (node (ref "SV1") (pin "3") (pinfunction "3_3") (pintype "passive"))
    )
    (net (code "48") (name "/OUT3") (class "Default")
      (node (ref "R13") (pin "2") (pinfunction "2_2") (pintype "passive"))
      (node (ref "R14") (pin "2") (pinfunction "2_2") (pintype "passive"))
      (node (ref "SV1") (pin "4") (pinfunction "4_4") (pintype "passive"))
    )
    (net (code "49") (name "/OUT4") (class "Default")
      (node (ref "R11") (pin "2") (pinfunction "2_2") (pintype "passive"))
      (node (ref "R12") (pin "2") (pinfunction "2_2") (pintype "passive"))
      (node (ref "SV1") (pin "5") (pinfunction "5_5") (pintype "passive"))
    )
    (net (code "50") (name "/OUT5") (class "Default")
      (node (ref "R10") (pin "2") (pinfunction "2_2") (pintype "passive"))
      (node (ref "R9") (pin "2") (pinfunction "2_2") (pintype "passive"))
      (node (ref "SV1") (pin "6") (pinfunction "6_6") (pintype "passive"))
    )
    (net (code "51") (name "/OUT6") (class "Default")
      (node (ref "R3") (pin "2") (pinfunction "2_2") (pintype "passive"))
      (node (ref "R4") (pin "2") (pinfunction "2_2") (pintype "passive"))
      (node (ref "SV1") (pin "7") (pinfunction "7_7") (pintype "passive"))
    )
    (net (code "52") (name "/OUT7") (class "Default")
      (node (ref "R1") (pin "2") (pinfunction "2_2") (pintype "passive"))
      (node (ref "R2") (pin "2") (pinfunction "2_2") (pintype "passive"))
      (node (ref "SV1") (pin "8") (pinfunction "8_8") (pintype "passive"))
    )
    (net (code "53") (name "/OUT8") (class "Default")
      (node (ref "R23") (pin "2") (pinfunction "2_2") (pintype "passive"))
      (node (ref "R24") (pin "2") (pinfunction "2_2") (pintype "passive"))
      (node (ref "SV1") (pin "9") (pinfunction "9_9") (pintype "passive"))
    )
    (net (code "54") (name "/OUT9") (class "Default")
      (node (ref "R21") (pin "2") (pinfunction "2_2") (pintype "passive"))
      (node (ref "R22") (pin "2") (pinfunction "2_2") (pintype "passive"))
      (node (ref "SV1") (pin "10") (pinfunction "10_10") (pintype "passive"))
    )
    (net (code "55") (name "/OUT10") (class "Default")
      (node (ref "R31") (pin "2") (pinfunction "2_2") (pintype "passive"))
      (node (ref "R32") (pin "2") (pinfunction "2_2") (pintype "passive"))
      (node (ref "SV1") (pin "11") (pinfunction "11_11") (pintype "passive"))
    )
    (net (code "56") (name "/OUT11") (class "Default")
      (node (ref "R29") (pin "2") (pinfunction "2_2") (pintype "passive"))
      (node (ref "R30") (pin "2") (pinfunction "2_2") (pintype "passive"))
      (node (ref "SV1") (pin "12") (pinfunction "12_12") (pintype "passive"))
    )
    (net (code "57") (name "/OUT12") (class "Default")
      (node (ref "R27") (pin "2") (pinfunction "2_2") (pintype "passive"))
      (node (ref "R28") (pin "2") (pinfunction "2_2") (pintype "passive"))
      (node (ref "SV1") (pin "13") (pinfunction "13_13") (pintype "passive"))
    )
    (net (code "58") (name "/OUT13") (class "Default")
      (node (ref "R25") (pin "2") (pinfunction "2_2") (pintype "passive"))
      (node (ref "R26") (pin "2") (pinfunction "2_2") (pintype "passive"))
      (node (ref "SV1") (pin "14") (pinfunction "14_14") (pintype "passive"))
    )
    (net (code "59") (name "/OUT14") (class "Default")
      (node (ref "R19") (pin "2") (pinfunction "2_2") (pintype "passive"))
      (node (ref "R20") (pin "2") (pinfunction "2_2") (pintype "passive"))
      (node (ref "SV1") (pin "15") (pinfunction "15_15") (pintype "passive"))
    )
    (net (code "60") (name "/OUT15") (class "Default")
      (node (ref "R17") (pin "2") (pinfunction "2_2") (pintype "passive"))
      (node (ref "R18") (pin "2") (pinfunction "2_2") (pintype "passive"))
      (node (ref "SV1") (pin "16") (pinfunction "16_16") (pintype "passive"))
    )
    (net (code "61") (name "/OUT16") (class "Default")
      (node (ref "R39") (pin "2") (pinfunction "2_2") (pintype "passive"))
      (node (ref "R40") (pin "2") (pinfunction "2_2") (pintype "passive"))
      (node (ref "SV1") (pin "17") (pinfunction "17_17") (pintype "passive"))
    )
    (net (code "62") (name "/OUT17") (class "Default")
      (node (ref "R37") (pin "2") (pinfunction "2_2") (pintype "passive"))
      (node (ref "R38") (pin "2") (pinfunction "2_2") (pintype "passive"))
      (node (ref "SV1") (pin "18") (pinfunction "18_18") (pintype "passive"))
    )
    (net (code "63") (name "/OUT18") (class "Default")
      (node (ref "R47") (pin "2") (pinfunction "2_2") (pintype "passive"))
      (node (ref "R48") (pin "2") (pinfunction "2_2") (pintype "passive"))
      (node (ref "SV1") (pin "19") (pinfunction "19_19") (pintype "passive"))
    )
    (net (code "64") (name "/OUT19") (class "Default")
      (node (ref "R45") (pin "2") (pinfunction "2_2") (pintype "passive"))
      (node (ref "R46") (pin "2") (pinfunction "2_2") (pintype "passive"))
      (node (ref "SV1") (pin "20") (pinfunction "20_20") (pintype "passive"))
    )
    (net (code "65") (name "/OUT20") (class "Default")
      (node (ref "R43") (pin "2") (pinfunction "2_2") (pintype "passive"))
      (node (ref "R44") (pin "2") (pinfunction "2_2") (pintype "passive"))
      (node (ref "SV1") (pin "21") (pinfunction "21_21") (pintype "passive"))
    )
    (net (code "66") (name "/OUT21") (class "Default")
      (node (ref "R41") (pin "2") (pinfunction "2_2") (pintype "passive"))
      (node (ref "R42") (pin "2") (pinfunction "2_2") (pintype "passive"))
      (node (ref "SV1") (pin "22") (pinfunction "22_22") (pintype "passive"))
    )
    (net (code "67") (name "/OUT22") (class "Default")
      (node (ref "R35") (pin "2") (pinfunction "2_2") (pintype "passive"))
      (node (ref "R36") (pin "2") (pinfunction "2_2") (pintype "passive"))
      (node (ref "SV1") (pin "23") (pinfunction "23_23") (pintype "passive"))
    )
    (net (code "68") (name "/OUT23") (class "Default")
      (node (ref "R33") (pin "2") (pinfunction "2_2") (pintype "passive"))
      (node (ref "R34") (pin "2") (pinfunction "2_2") (pintype "passive"))
      (node (ref "SV1") (pin "24") (pinfunction "24_24") (pintype "passive"))
    )
    (net (code "69") (name "/OUT24") (class "Default")
      (node (ref "R55") (pin "2") (pinfunction "2_2") (pintype "passive"))
      (node (ref "R56") (pin "2") (pinfunction "2_2") (pintype "passive"))
      (node (ref "SV1") (pin "25") (pinfunction "25_25") (pintype "passive"))
    )
    (net (code "70") (name "/OUT25") (class "Default")
      (node (ref "R53") (pin "2") (pinfunction "2_2") (pintype "passive"))
      (node (ref "R54") (pin "2") (pinfunction "2_2") (pintype "passive"))
      (node (ref "SV1") (pin "26") (pinfunction "26_26") (pintype "passive"))
    )
    (net (code "71") (name "/OUT26") (class "Default")
      (node (ref "R63") (pin "2") (pinfunction "2_2") (pintype "passive"))
      (node (ref "R64") (pin "2") (pinfunction "2_2") (pintype "passive"))
      (node (ref "SV1") (pin "27") (pinfunction "27_27") (pintype "passive"))
    )
    (net (code "72") (name "/OUT27") (class "Default")
      (node (ref "R61") (pin "2") (pinfunction "2_2") (pintype "passive"))
      (node (ref "R62") (pin "2") (pinfunction "2_2") (pintype "passive"))
      (node (ref "SV1") (pin "28") (pinfunction "28_28") (pintype "passive"))
    )
    (net (code "73") (name "/OUT28") (class "Default")
      (node (ref "R59") (pin "2") (pinfunction "2_2") (pintype "passive"))
      (node (ref "R60") (pin "2") (pinfunction "2_2") (pintype "passive"))
      (node (ref "SV1") (pin "29") (pinfunction "29_29") (pintype "passive"))
    )
    (net (code "74") (name "/OUT29") (class "Default")
      (node (ref "R57") (pin "2") (pinfunction "2_2") (pintype "passive"))
      (node (ref "R58") (pin "2") (pinfunction "2_2") (pintype "passive"))
      (node (ref "SV1") (pin "30") (pinfunction "30_30") (pintype "passive"))
    )
    (net (code "75") (name "/OUT30") (class "Default")
      (node (ref "R51") (pin "2") (pinfunction "2_2") (pintype "passive"))
      (node (ref "R52") (pin "2") (pinfunction "2_2") (pintype "passive"))
      (node (ref "SV1") (pin "31") (pinfunction "31_31") (pintype "passive"))
    )
    (net (code "76") (name "/OUT31") (class "Default")
      (node (ref "R49") (pin "2") (pinfunction "2_2") (pintype "passive"))
      (node (ref "R50") (pin "2") (pinfunction "2_2") (pintype "passive"))
      (node (ref "SV1") (pin "32") (pinfunction "32_32") (pintype "passive"))
    )
    (net (code "77") (name "AGND") (class "Default")
      (node (ref "C1") (pin "1") (pinfunction "1_1") (pintype "passive"))
      (node (ref "C10") (pin "1") (pinfunction "1_1") (pintype "passive"))
      (node (ref "C11") (pin "1") (pinfunction "1_1") (pintype "passive"))
      (node (ref "C17") (pin "1") (pinfunction "1_1") (pintype "passive"))
      (node (ref "C18") (pin "1") (pinfunction "1_1") (pintype "passive"))
      (node (ref "C19") (pin "1") (pinfunction "1_1") (pintype "passive"))
      (node (ref "C2") (pin "1") (pinfunction "1_1") (pintype "passive"))
      (node (ref "C20") (pin "1") (pinfunction "1_1") (pintype "passive"))
      (node (ref "C27") (pin "1") (pinfunction "1_1") (pintype "passive"))
      (node (ref "C28") (pin "1") (pinfunction "1_1") (pintype "passive"))
      (node (ref "C29") (pin "1") (pinfunction "1_1") (pintype "passive"))
      (node (ref "C3") (pin "1") (pinfunction "1_1") (pintype "passive"))
      (node (ref "C30") (pin "1") (pinfunction "1_1") (pintype "passive"))
      (node (ref "C37") (pin "1") (pinfunction "1_1") (pintype "passive"))
      (node (ref "C38") (pin "1") (pinfunction "1_1") (pintype "passive"))
      (node (ref "C39") (pin "1") (pinfunction "1_1") (pintype "passive"))
      (node (ref "C4") (pin "1") (pinfunction "1_1") (pintype "passive"))
      (node (ref "C40") (pin "1") (pinfunction "1_1") (pintype "passive"))
      (node (ref "C46") (pin "1") (pinfunction "1_1") (pintype "passive"))
      (node (ref "C47") (pin "1") (pinfunction "1_1") (pintype "passive"))
      (node (ref "C48") (pin "1") (pinfunction "1_1") (pintype "passive"))
      (node (ref "C49") (pin "1") (pinfunction "1_1") (pintype "passive"))
      (node (ref "C55") (pin "1") (pinfunction "1_1") (pintype "passive"))
      (node (ref "C56") (pin "1") (pinfunction "1_1") (pintype "passive"))
      (node (ref "C57") (pin "1") (pinfunction "1_1") (pintype "passive"))
      (node (ref "C58") (pin "1") (pinfunction "1_1") (pintype "passive"))
      (node (ref "C64") (pin "1") (pinfunction "1_1") (pintype "passive"))
      (node (ref "C65") (pin "1") (pinfunction "1_1") (pintype "passive"))
      (node (ref "C66") (pin "1") (pinfunction "1_1") (pintype "passive"))
      (node (ref "C67") (pin "1") (pinfunction "1_1") (pintype "passive"))
      (node (ref "C75") (pin "+") (pinfunction "+_+") (pintype "passive"))
      (node (ref "C76") (pin "-") (pinfunction "-_-") (pintype "passive"))
      (node (ref "C8") (pin "1") (pinfunction "1_1") (pintype "passive"))
      (node (ref "C9") (pin "1") (pinfunction "1_1") (pintype "passive"))
      (node (ref "IC10") (pin "12") (pinfunction "GND_12") (pintype "power_in"))
      (node (ref "IC9") (pin "12") (pinfunction "GND_12") (pintype "power_in"))
      (node (ref "IO-AN") (pin "5") (pinfunction "5_5") (pintype "passive"))
      (node (ref "J1") (pin "2") (pinfunction "S_2") (pintype "passive"))
      (node (ref "SV1") (pin "34") (pinfunction "34_34") (pintype "passive"))
    )
    (net (code "78") (name "Net-(IC1A--IN)") (class "Default")
      (node (ref "C33") (pin "2") (pinfunction "2_2") (pintype "passive"))
      (node (ref "IC1") (pin "2") (pinfunction "-IN_2") (pintype "input"))
      (node (ref "R2") (pin "1") (pinfunction "1_1") (pintype "passive"))
    )
    (net (code "79") (name "Net-(IC1A-OUT)") (class "Default")
      (node (ref "C33") (pin "1") (pinfunction "1_1") (pintype "passive"))
      (node (ref "IC1") (pin "1") (pinfunction "OUT_1") (pintype "output"))
      (node (ref "R1") (pin "1") (pinfunction "1_1") (pintype "passive"))
    )
    (net (code "80") (name "Net-(IC1B--IN)") (class "Default")
      (node (ref "C34") (pin "2") (pinfunction "2_2") (pintype "passive"))
      (node (ref "IC1") (pin "6") (pinfunction "-IN_6") (pintype "input"))
      (node (ref "R4") (pin "1") (pinfunction "1_1") (pintype "passive"))
    )
    (net (code "81") (name "Net-(IC1B-OUT)") (class "Default")
      (node (ref "C34") (pin "1") (pinfunction "1_1") (pintype "passive"))
      (node (ref "IC1") (pin "7") (pinfunction "OUT_7") (pintype "output"))
      (node (ref "R3") (pin "1") (pinfunction "1_1") (pintype "passive"))
    )
    (net (code "82") (name "Net-(IC1C--IN)") (class "Default")
      (node (ref "C5") (pin "2") (pinfunction "2_2") (pintype "passive"))
      (node (ref "IC1") (pin "9") (pinfunction "-IN_9") (pintype "input"))
      (node (ref "R6") (pin "1") (pinfunction "1_1") (pintype "passive"))
    )
    (net (code "83") (name "Net-(IC1C-OUT)") (class "Default")
      (node (ref "C5") (pin "1") (pinfunction "1_1") (pintype "passive"))
      (node (ref "IC1") (pin "8") (pinfunction "OUT_8") (pintype "output"))
      (node (ref "R5") (pin "1") (pinfunction "1_1") (pintype "passive"))
    )
    (net (code "84") (name "Net-(IC1D--IN)") (class "Default")
      (node (ref "C6") (pin "2") (pinfunction "2_2") (pintype "passive"))
      (node (ref "IC1") (pin "13") (pinfunction "-IN_13") (pintype "input"))
      (node (ref "R7") (pin "1") (pinfunction "1_1") (pintype "passive"))
    )
    (net (code "85") (name "Net-(IC1D-OUT)") (class "Default")
      (node (ref "C6") (pin "1") (pinfunction "1_1") (pintype "passive"))
      (node (ref "IC1") (pin "14") (pinfunction "OUT_14") (pintype "output"))
      (node (ref "R8") (pin "1") (pinfunction "1_1") (pintype "passive"))
    )
    (net (code "86") (name "Net-(IC2A--IN)") (class "Default")
      (node (ref "C12") (pin "2") (pinfunction "2_2") (pintype "passive"))
      (node (ref "IC2") (pin "2") (pinfunction "-IN_2") (pintype "input"))
      (node (ref "R10") (pin "1") (pinfunction "1_1") (pintype "passive"))
    )
    (net (code "87") (name "Net-(IC2A-OUT)") (class "Default")
      (node (ref "C12") (pin "1") (pinfunction "1_1") (pintype "passive"))
      (node (ref "IC2") (pin "1") (pinfunction "OUT_1") (pintype "output"))
      (node (ref "R9") (pin "1") (pinfunction "1_1") (pintype "passive"))
    )
    (net (code "88") (name "Net-(IC2B--IN)") (class "Default")
      (node (ref "C13") (pin "2") (pinfunction "2_2") (pintype "passive"))
      (node (ref "IC2") (pin "6") (pinfunction "-IN_6") (pintype "input"))
      (node (ref "R12") (pin "1") (pinfunction "1_1") (pintype "passive"))
    )
    (net (code "89") (name "Net-(IC2B-OUT)") (class "Default")
      (node (ref "C13") (pin "1") (pinfunction "1_1") (pintype "passive"))
      (node (ref "IC2") (pin "7") (pinfunction "OUT_7") (pintype "output"))
      (node (ref "R11") (pin "1") (pinfunction "1_1") (pintype "passive"))
    )
    (net (code "90") (name "Net-(IC2C--IN)") (class "Default")
      (node (ref "C14") (pin "2") (pinfunction "2_2") (pintype "passive"))
      (node (ref "IC2") (pin "9") (pinfunction "-IN_9") (pintype "input"))
      (node (ref "R14") (pin "1") (pinfunction "1_1") (pintype "passive"))
    )
    (net (code "91") (name "Net-(IC2C-OUT)") (class "Default")
      (node (ref "C14") (pin "1") (pinfunction "1_1") (pintype "passive"))
      (node (ref "IC2") (pin "8") (pinfunction "OUT_8") (pintype "output"))
      (node (ref "R13") (pin "1") (pinfunction "1_1") (pintype "passive"))
    )
    (net (code "92") (name "Net-(IC2D--IN)") (class "Default")
      (node (ref "C15") (pin "2") (pinfunction "2_2") (pintype "passive"))
      (node (ref "IC2") (pin "13") (pinfunction "-IN_13") (pintype "input"))
      (node (ref "R15") (pin "1") (pinfunction "1_1") (pintype "passive"))
    )
    (net (code "93") (name "Net-(IC2D-OUT)") (class "Default")
      (node (ref "C15") (pin "1") (pinfunction "1_1") (pintype "passive"))
      (node (ref "IC2") (pin "14") (pinfunction "OUT_14") (pintype "output"))
      (node (ref "R16") (pin "1") (pinfunction "1_1") (pintype "passive"))
    )
    (net (code "94") (name "Net-(IC3A--IN)") (class "Default")
      (node (ref "C21") (pin "2") (pinfunction "2_2") (pintype "passive"))
      (node (ref "IC3") (pin "2") (pinfunction "-IN_2") (pintype "input"))
      (node (ref "R18") (pin "1") (pinfunction "1_1") (pintype "passive"))
    )
    (net (code "95") (name "Net-(IC3A-OUT)") (class "Default")
      (node (ref "C21") (pin "1") (pinfunction "1_1") (pintype "passive"))
      (node (ref "IC3") (pin "1") (pinfunction "OUT_1") (pintype "output"))
      (node (ref "R17") (pin "1") (pinfunction "1_1") (pintype "passive"))
    )
    (net (code "96") (name "Net-(IC3B--IN)") (class "Default")
      (node (ref "C22") (pin "2") (pinfunction "2_2") (pintype "passive"))
      (node (ref "IC3") (pin "6") (pinfunction "-IN_6") (pintype "input"))
      (node (ref "R20") (pin "1") (pinfunction "1_1") (pintype "passive"))
    )
    (net (code "97") (name "Net-(IC3B-OUT)") (class "Default")
      (node (ref "C22") (pin "1") (pinfunction "1_1") (pintype "passive"))
      (node (ref "IC3") (pin "7") (pinfunction "OUT_7") (pintype "output"))
      (node (ref "R19") (pin "1") (pinfunction "1_1") (pintype "passive"))
    )
    (net (code "98") (name "Net-(IC3C--IN)") (class "Default")
      (node (ref "C23") (pin "2") (pinfunction "2_2") (pintype "passive"))
      (node (ref "IC3") (pin "9") (pinfunction "-IN_9") (pintype "input"))
      (node (ref "R22") (pin "1") (pinfunction "1_1") (pintype "passive"))
    )
    (net (code "99") (name "Net-(IC3C-OUT)") (class "Default")
      (node (ref "C23") (pin "1") (pinfunction "1_1") (pintype "passive"))
      (node (ref "IC3") (pin "8") (pinfunction "OUT_8") (pintype "output"))
      (node (ref "R21") (pin "1") (pinfunction "1_1") (pintype "passive"))
    )
    (net (code "100") (name "Net-(IC3D--IN)") (class "Default")
      (node (ref "C24") (pin "2") (pinfunction "2_2") (pintype "passive"))
      (node (ref "IC3") (pin "13") (pinfunction "-IN_13") (pintype "input"))
      (node (ref "R23") (pin "1") (pinfunction "1_1") (pintype "passive"))
    )
    (net (code "101") (name "Net-(IC3D-OUT)") (class "Default")
      (node (ref "C24") (pin "1") (pinfunction "1_1") (pintype "passive"))
      (node (ref "IC3") (pin "14") (pinfunction "OUT_14") (pintype "output"))
      (node (ref "R24") (pin "1") (pinfunction "1_1") (pintype "passive"))
    )
    (net (code "102") (name "Net-(IC4A--IN)") (class "Default")
      (node (ref "C41") (pin "2") (pinfunction "2_2") (pintype "passive"))
      (node (ref "IC4") (pin "2") (pinfunction "-IN_2") (pintype "input"))
      (node (ref "R34") (pin "1") (pinfunction "1_1") (pintype "passive"))
    )
    (net (code "103") (name "Net-(IC4A-OUT)") (class "Default")
      (node (ref "C41") (pin "1") (pinfunction "1_1") (pintype "passive"))
      (node (ref "IC4") (pin "1") (pinfunction "OUT_1") (pintype "output"))
      (node (ref "R33") (pin "1") (pinfunction "1_1") (pintype "passive"))
    )
    (net (code "104") (name "Net-(IC4B--IN)") (class "Default")
      (node (ref "C42") (pin "2") (pinfunction "2_2") (pintype "passive"))
      (node (ref "IC4") (pin "6") (pinfunction "-IN_6") (pintype "input"))
      (node (ref "R36") (pin "1") (pinfunction "1_1") (pintype "passive"))
    )
    (net (code "105") (name "Net-(IC4B-OUT)") (class "Default")
      (node (ref "C42") (pin "1") (pinfunction "1_1") (pintype "passive"))
      (node (ref "IC4") (pin "7") (pinfunction "OUT_7") (pintype "output"))
      (node (ref "R35") (pin "1") (pinfunction "1_1") (pintype "passive"))
    )
    (net (code "106") (name "Net-(IC4C--IN)") (class "Default")
      (node (ref "C43") (pin "2") (pinfunction "2_2") (pintype "passive"))
      (node (ref "IC4") (pin "9") (pinfunction "-IN_9") (pintype "input"))
      (node (ref "R38") (pin "1") (pinfunction "1_1") (pintype "passive"))
    )
    (net (code "107") (name "Net-(IC4C-OUT)") (class "Default")
      (node (ref "C43") (pin "1") (pinfunction "1_1") (pintype "passive"))
      (node (ref "IC4") (pin "8") (pinfunction "OUT_8") (pintype "output"))
      (node (ref "R37") (pin "1") (pinfunction "1_1") (pintype "passive"))
    )
    (net (code "108") (name "Net-(IC4D--IN)") (class "Default")
      (node (ref "C44") (pin "2") (pinfunction "2_2") (pintype "passive"))
      (node (ref "IC4") (pin "13") (pinfunction "-IN_13") (pintype "input"))
      (node (ref "R39") (pin "1") (pinfunction "1_1") (pintype "passive"))
    )
    (net (code "109") (name "Net-(IC4D-OUT)") (class "Default")
      (node (ref "C44") (pin "1") (pinfunction "1_1") (pintype "passive"))
      (node (ref "IC4") (pin "14") (pinfunction "OUT_14") (pintype "output"))
      (node (ref "R40") (pin "1") (pinfunction "1_1") (pintype "passive"))
    )
    (net (code "110") (name "Net-(IC5A--IN)") (class "Default")
      (node (ref "C31") (pin "2") (pinfunction "2_2") (pintype "passive"))
      (node (ref "IC5") (pin "2") (pinfunction "-IN_2") (pintype "input"))
      (node (ref "R26") (pin "1") (pinfunction "1_1") (pintype "passive"))
    )
    (net (code "111") (name "Net-(IC5A-OUT)") (class "Default")
      (node (ref "C31") (pin "1") (pinfunction "1_1") (pintype "passive"))
      (node (ref "IC5") (pin "1") (pinfunction "OUT_1") (pintype "output"))
      (node (ref "R25") (pin "1") (pinfunction "1_1") (pintype "passive"))
    )
    (net (code "112") (name "Net-(IC5B--IN)") (class "Default")
      (node (ref "C32") (pin "2") (pinfunction "2_2") (pintype "passive"))
      (node (ref "IC5") (pin "6") (pinfunction "-IN_6") (pintype "input"))
      (node (ref "R28") (pin "1") (pinfunction "1_1") (pintype "passive"))
    )
    (net (code "113") (name "Net-(IC5B-OUT)") (class "Default")
      (node (ref "C32") (pin "1") (pinfunction "1_1") (pintype "passive"))
      (node (ref "IC5") (pin "7") (pinfunction "OUT_7") (pintype "output"))
      (node (ref "R27") (pin "1") (pinfunction "1_1") (pintype "passive"))
    )
    (net (code "114") (name "Net-(IC5C--IN)") (class "Default")
      (node (ref "C35") (pin "2") (pinfunction "2_2") (pintype "passive"))
      (node (ref "IC5") (pin "9") (pinfunction "-IN_9") (pintype "input"))
      (node (ref "R30") (pin "1") (pinfunction "1_1") (pintype "passive"))
    )
    (net (code "115") (name "Net-(IC5C-OUT)") (class "Default")
      (node (ref "C35") (pin "1") (pinfunction "1_1") (pintype "passive"))
      (node (ref "IC5") (pin "8") (pinfunction "OUT_8") (pintype "output"))
      (node (ref "R29") (pin "1") (pinfunction "1_1") (pintype "passive"))
    )
    (net (code "116") (name "Net-(IC5D--IN)") (class "Default")
      (node (ref "C36") (pin "2") (pinfunction "2_2") (pintype "passive"))
      (node (ref "IC5") (pin "13") (pinfunction "-IN_13") (pintype "input"))
      (node (ref "R31") (pin "1") (pinfunction "1_1") (pintype "passive"))
    )
    (net (code "117") (name "Net-(IC5D-OUT)") (class "Default")
      (node (ref "C36") (pin "1") (pinfunction "1_1") (pintype "passive"))
      (node (ref "IC5") (pin "14") (pinfunction "OUT_14") (pintype "output"))
      (node (ref "R32") (pin "1") (pinfunction "1_1") (pintype "passive"))
    )
    (net (code "118") (name "Net-(IC6A--IN)") (class "Default")
      (node (ref "C50") (pin "2") (pinfunction "2_2") (pintype "passive"))
      (node (ref "IC6") (pin "2") (pinfunction "-IN_2") (pintype "input"))
      (node (ref "R42") (pin "1") (pinfunction "1_1") (pintype "passive"))
    )
    (net (code "119") (name "Net-(IC6A-OUT)") (class "Default")
      (node (ref "C50") (pin "1") (pinfunction "1_1") (pintype "passive"))
      (node (ref "IC6") (pin "1") (pinfunction "OUT_1") (pintype "output"))
      (node (ref "R41") (pin "1") (pinfunction "1_1") (pintype "passive"))
    )
    (net (code "120") (name "Net-(IC6B--IN)") (class "Default")
      (node (ref "C51") (pin "2") (pinfunction "2_2") (pintype "passive"))
      (node (ref "IC6") (pin "6") (pinfunction "-IN_6") (pintype "input"))
      (node (ref "R44") (pin "1") (pinfunction "1_1") (pintype "passive"))
    )
    (net (code "121") (name "Net-(IC6B-OUT)") (class "Default")
      (node (ref "C51") (pin "1") (pinfunction "1_1") (pintype "passive"))
      (node (ref "IC6") (pin "7") (pinfunction "OUT_7") (pintype "output"))
      (node (ref "R43") (pin "1") (pinfunction "1_1") (pintype "passive"))
    )
    (net (code "122") (name "Net-(IC6C--IN)") (class "Default")
      (node (ref "C52") (pin "2") (pinfunction "2_2") (pintype "passive"))
      (node (ref "IC6") (pin "9") (pinfunction "-IN_9") (pintype "input"))
      (node (ref "R46") (pin "1") (pinfunction "1_1") (pintype "passive"))
    )
    (net (code "123") (name "Net-(IC6C-OUT)") (class "Default")
      (node (ref "C52") (pin "1") (pinfunction "1_1") (pintype "passive"))
      (node (ref "IC6") (pin "8") (pinfunction "OUT_8") (pintype "output"))
      (node (ref "R45") (pin "1") (pinfunction "1_1") (pintype "passive"))
    )
    (net (code "124") (name "Net-(IC6D--IN)") (class "Default")
      (node (ref "C53") (pin "2") (pinfunction "2_2") (pintype "passive"))
      (node (ref "IC6") (pin "13") (pinfunction "-IN_13") (pintype "input"))
      (node (ref "R47") (pin "1") (pinfunction "1_1") (pintype "passive"))
    )
    (net (code "125") (name "Net-(IC6D-OUT)") (class "Default")
      (node (ref "C53") (pin "1") (pinfunction "1_1") (pintype "passive"))
      (node (ref "IC6") (pin "14") (pinfunction "OUT_14") (pintype "output"))
      (node (ref "R48") (pin "1") (pinfunction "1_1") (pintype "passive"))
    )
    (net (code "126") (name "Net-(IC7A--IN)") (class "Default")
      (node (ref "C59") (pin "2") (pinfunction "2_2") (pintype "passive"))
      (node (ref "IC7") (pin "2") (pinfunction "-IN_2") (pintype "input"))
      (node (ref "R50") (pin "1") (pinfunction "1_1") (pintype "passive"))
    )
    (net (code "127") (name "Net-(IC7A-OUT)") (class "Default")
      (node (ref "C59") (pin "1") (pinfunction "1_1") (pintype "passive"))
      (node (ref "IC7") (pin "1") (pinfunction "OUT_1") (pintype "output"))
      (node (ref "R49") (pin "1") (pinfunction "1_1") (pintype "passive"))
    )
    (net (code "128") (name "Net-(IC7B--IN)") (class "Default")
      (node (ref "C60") (pin "2") (pinfunction "2_2") (pintype "passive"))
      (node (ref "IC7") (pin "6") (pinfunction "-IN_6") (pintype "input"))
      (node (ref "R52") (pin "1") (pinfunction "1_1") (pintype "passive"))
    )
    (net (code "129") (name "Net-(IC7B-OUT)") (class "Default")
      (node (ref "C60") (pin "1") (pinfunction "1_1") (pintype "passive"))
      (node (ref "IC7") (pin "7") (pinfunction "OUT_7") (pintype "output"))
      (node (ref "R51") (pin "1") (pinfunction "1_1") (pintype "passive"))
    )
    (net (code "130") (name "Net-(IC7C--IN)") (class "Default")
      (node (ref "C61") (pin "2") (pinfunction "2_2") (pintype "passive"))
      (node (ref "IC7") (pin "9") (pinfunction "-IN_9") (pintype "input"))
      (node (ref "R54") (pin "1") (pinfunction "1_1") (pintype "passive"))
    )
    (net (code "131") (name "Net-(IC7C-OUT)") (class "Default")
      (node (ref "C61") (pin "1") (pinfunction "1_1") (pintype "passive"))
      (node (ref "IC7") (pin "8") (pinfunction "OUT_8") (pintype "output"))
      (node (ref "R53") (pin "1") (pinfunction "1_1") (pintype "passive"))
    )
    (net (code "132") (name "Net-(IC7D--IN)") (class "Default")
      (node (ref "C62") (pin "2") (pinfunction "2_2") (pintype "passive"))
      (node (ref "IC7") (pin "13") (pinfunction "-IN_13") (pintype "input"))
      (node (ref "R55") (pin "1") (pinfunction "1_1") (pintype "passive"))
    )
    (net (code "133") (name "Net-(IC7D-OUT)") (class "Default")
      (node (ref "C62") (pin "1") (pinfunction "1_1") (pintype "passive"))
      (node (ref "IC7") (pin "14") (pinfunction "OUT_14") (pintype "output"))
      (node (ref "R56") (pin "1") (pinfunction "1_1") (pintype "passive"))
    )
    (net (code "134") (name "Net-(IC8A--IN)") (class "Default")
      (node (ref "C68") (pin "2") (pinfunction "2_2") (pintype "passive"))
      (node (ref "IC8") (pin "2") (pinfunction "-IN_2") (pintype "input"))
      (node (ref "R58") (pin "1") (pinfunction "1_1") (pintype "passive"))
    )
    (net (code "135") (name "Net-(IC8A-OUT)") (class "Default")
      (node (ref "C68") (pin "1") (pinfunction "1_1") (pintype "passive"))
      (node (ref "IC8") (pin "1") (pinfunction "OUT_1") (pintype "output"))
      (node (ref "R57") (pin "1") (pinfunction "1_1") (pintype "passive"))
    )
    (net (code "136") (name "Net-(IC8B--IN)") (class "Default")
      (node (ref "C69") (pin "2") (pinfunction "2_2") (pintype "passive"))
      (node (ref "IC8") (pin "6") (pinfunction "-IN_6") (pintype "input"))
      (node (ref "R60") (pin "1") (pinfunction "1_1") (pintype "passive"))
    )
    (net (code "137") (name "Net-(IC8B-OUT)") (class "Default")
      (node (ref "C69") (pin "1") (pinfunction "1_1") (pintype "passive"))
      (node (ref "IC8") (pin "7") (pinfunction "OUT_7") (pintype "output"))
      (node (ref "R59") (pin "1") (pinfunction "1_1") (pintype "passive"))
    )
    (net (code "138") (name "Net-(IC8C--IN)") (class "Default")
      (node (ref "C70") (pin "2") (pinfunction "2_2") (pintype "passive"))
      (node (ref "IC8") (pin "9") (pinfunction "-IN_9") (pintype "input"))
      (node (ref "R62") (pin "1") (pinfunction "1_1") (pintype "passive"))
    )
    (net (code "139") (name "Net-(IC8C-OUT)") (class "Default")
      (node (ref "C70") (pin "1") (pinfunction "1_1") (pintype "passive"))
      (node (ref "IC8") (pin "8") (pinfunction "OUT_8") (pintype "output"))
      (node (ref "R61") (pin "1") (pinfunction "1_1") (pintype "passive"))
    )
    (net (code "140") (name "Net-(IC8D--IN)") (class "Default")
      (node (ref "C71") (pin "2") (pinfunction "2_2") (pintype "passive"))
      (node (ref "IC8") (pin "13") (pinfunction "-IN_13") (pintype "input"))
      (node (ref "R63") (pin "1") (pinfunction "1_1") (pintype "passive"))
    )
    (net (code "141") (name "Net-(IC8D-OUT)") (class "Default")
      (node (ref "C71") (pin "1") (pinfunction "1_1") (pintype "passive"))
      (node (ref "IC8") (pin "14") (pinfunction "OUT_14") (pintype "output"))
      (node (ref "R64") (pin "1") (pinfunction "1_1") (pintype "passive"))
    )
    (net (code "142") (name "V+") (class "Default")
      (node (ref "J1") (pin "1") (pinfunction "S_1") (pintype "passive"))
      (node (ref "R65") (pin "2") (pinfunction "2_2") (pintype "passive"))
      (node (ref "SV1") (pin "33") (pinfunction "33_33") (pintype "passive"))
    )
    (net (code "143") (name "V-") (class "Default")
      (node (ref "J1") (pin "3") (pinfunction "S_3") (pintype "passive"))
      (node (ref "R66") (pin "2") (pinfunction "2_2") (pintype "passive"))
      (node (ref "SV1") (pin "35") (pinfunction "35_35") (pintype "passive"))
    )
    (net (code "144") (name "unconnected-(IC9-NC-Pad2)") (class "Default")
      (node (ref "IC9") (pin "2") (pinfunction "NC_2") (pintype "no_connect"))
    )
    (net (code "145") (name "unconnected-(IC9-NC-Pad3)") (class "Default")
      (node (ref "IC9") (pin "3") (pinfunction "NC_3") (pintype "no_connect"))
    )
    (net (code "146") (name "unconnected-(IC9-NC-Pad13)") (class "Default")
      (node (ref "IC9") (pin "13") (pinfunction "NC_13") (pintype "no_connect"))
    )
    (net (code "147") (name "unconnected-(IC10-NC-Pad2)") (class "Default")
      (node (ref "IC10") (pin "2") (pinfunction "NC_2") (pintype "no_connect"))
    )
    (net (code "148") (name "unconnected-(IC10-NC-Pad3)") (class "Default")
      (node (ref "IC10") (pin "3") (pinfunction "NC_3") (pintype "no_connect"))
    )
    (net (code "149") (name "unconnected-(IC10-NC-Pad13)") (class "Default")
      (node (ref "IC10") (pin "13") (pinfunction "NC_13") (pintype "no_connect"))
    )
    (net (code "150") (name "unconnected-(IO-AN-Pad4)") (class "Default")
      (node (ref "IO-AN") (pin "4") (pinfunction "4_4") (pintype "passive"))
    )
    (net (code "151") (name "unconnected-(SV1-Pad36)") (class "Default")
      (node (ref "SV1") (pin "36") (pinfunction "36_36") (pintype "passive"))
    )
  )
)
